# usbSimInput.net
KiCad netlist of a schematic drawn in EAGLE
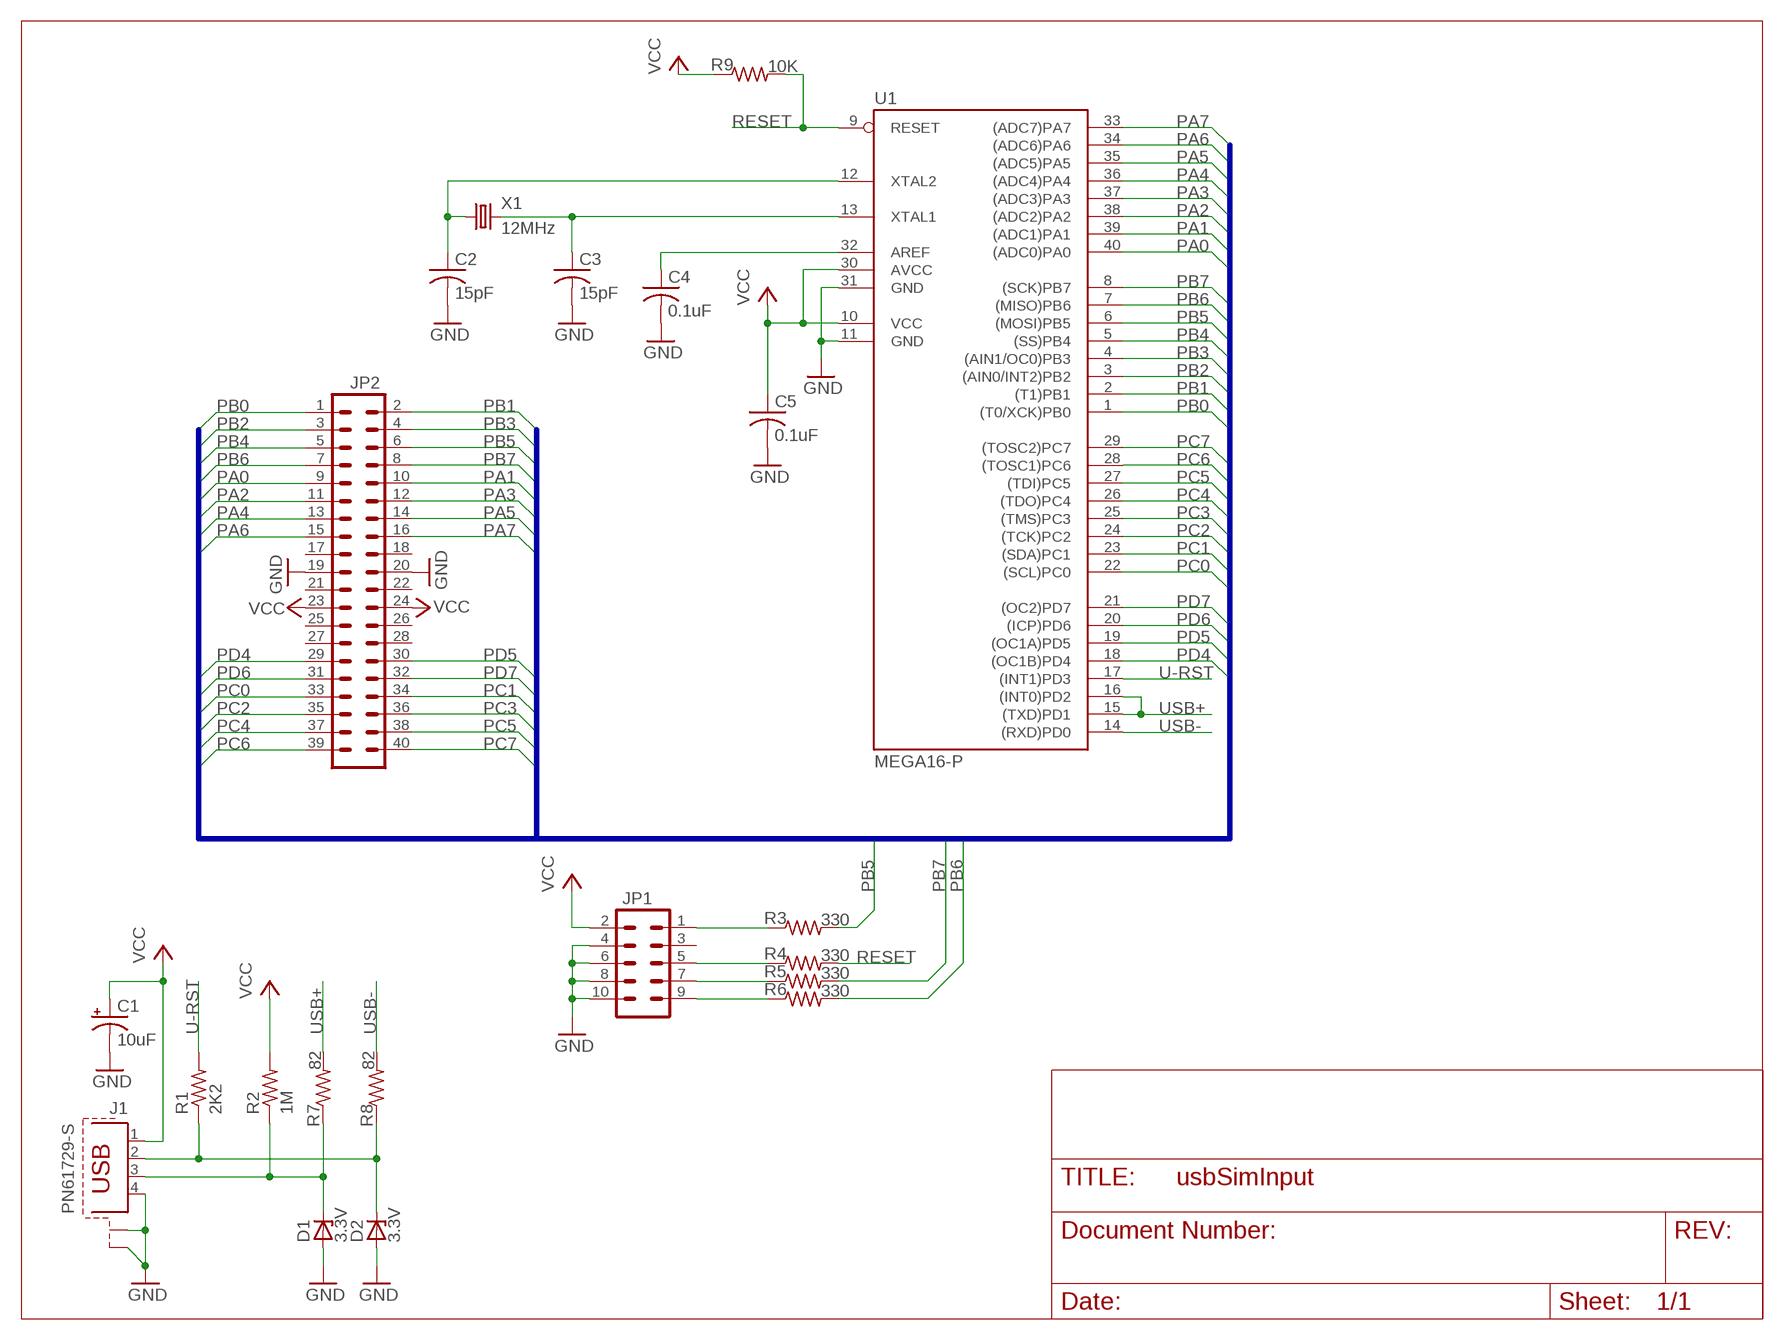
[diagram p0: schematic, sheet 1]

(export (version "E")
  (design (tool "Eeschema 10.0.6"))
  (components
    (comp (ref "C1")
      (value "10uF")
      (footprint "eagle-import:E2,5-5")
      (libsource (lib "eagle-import") (part "CPOL-USE2.5-5"))
    )
    (comp (ref "C2")
      (value "15pF")
      (footprint "eagle-import:C025-024X044")
      (libsource (lib "eagle-import") (part "C-US025-024X044"))
    )
    (comp (ref "C3")
      (value "15pF")
      (footprint "eagle-import:C025-024X044")
      (libsource (lib "eagle-import") (part "C-US025-024X044"))
    )
    (comp (ref "C4")
      (value "0.1uF")
      (footprint "eagle-import:C050-025X075")
      (libsource (lib "eagle-import") (part "C-US050-025X075"))
    )
    (comp (ref "C5")
      (value "0.1uF")
      (footprint "eagle-import:C050-025X075")
      (libsource (lib "eagle-import") (part "C-US050-025X075"))
    )
    (comp (ref "D1")
      (value "3.3V")
      (footprint "eagle-import:ZDIO-5")
      (libsource (lib "eagle-import") (part "ZENER-DIODEZD-5"))
    )
    (comp (ref "D2")
      (value "3.3V")
      (footprint "eagle-import:ZDIO-5")
      (libsource (lib "eagle-import") (part "ZENER-DIODEZD-5"))
    )
    (comp (ref "J1")
      (value "PN61729-S")
      (footprint "eagle-import:PN61729-S")
      (libsource (lib "eagle-import") (part "PN61729-S"))
    )
    (comp (ref "JP1")
      (value "ML10")
      (footprint "eagle-import:ML10")
      (libsource (lib "eagle-import") (part "ML10"))
    )
    (comp (ref "JP2")
      (value "MA20-2")
      (footprint "eagle-import:MA20-2")
      (libsource (lib "eagle-import") (part "MA20-2"))
    )
    (comp (ref "R1")
      (value "2K2")
      (footprint "eagle-import:0207_7")
      (libsource (lib "eagle-import") (part "R-US_0207/7"))
    )
    (comp (ref "R2")
      (value "1M")
      (footprint "eagle-import:0207_7")
      (libsource (lib "eagle-import") (part "R-US_0207/7"))
    )
    (comp (ref "R3")
      (value "330")
      (footprint "eagle-import:0207_7")
      (libsource (lib "eagle-import") (part "R-US_0207/7"))
    )
    (comp (ref "R4")
      (value "330")
      (footprint "eagle-import:0207_7")
      (libsource (lib "eagle-import") (part "R-US_0207/7"))
    )
    (comp (ref "R5")
      (value "330")
      (footprint "eagle-import:0207_7")
      (libsource (lib "eagle-import") (part "R-US_0207/7"))
    )
    (comp (ref "R6")
      (value "330")
      (footprint "eagle-import:0207_7")
      (libsource (lib "eagle-import") (part "R-US_0207/7"))
    )
    (comp (ref "R7")
      (value "82")
      (footprint "eagle-import:0207_7")
      (libsource (lib "eagle-import") (part "R-US_0207/7"))
    )
    (comp (ref "R8")
      (value "82")
      (footprint "eagle-import:0207_7")
      (libsource (lib "eagle-import") (part "R-US_0207/7"))
    )
    (comp (ref "R9")
      (value "10K")
      (footprint "eagle-import:0207_7")
      (libsource (lib "eagle-import") (part "R-US_0207/7"))
    )
    (comp (ref "U1")
      (value "MEGA16-P")
      (footprint "eagle-import:DIL40")
      (fields (field (name "MPN") "ATMEGA16-16PU"))
      (libsource (lib "eagle-import") (part "MEGA16-P"))
    )
    (comp (ref "X1")
      (value "12MHz")
      (footprint "eagle-import:HC49U-V")
      (libsource (lib "eagle-import") (part "CRYSTALHC49U-V"))
    )
  )
  (nets
    (net (code "1") (name "/PA0") (class "Default")
      (node (ref "JP2") (pin "9") (pinfunction "9_9") (pintype "passive"))
      (node (ref "U1") (pin "40") (pinfunction "(ADC0)PA0_40") (pintype "bidirectional"))
    )
    (net (code "2") (name "/PA1") (class "Default")
      (node (ref "JP2") (pin "10") (pinfunction "10_10") (pintype "passive"))
      (node (ref "U1") (pin "39") (pinfunction "(ADC1)PA1_39") (pintype "bidirectional"))
    )
    (net (code "3") (name "/PA2") (class "Default")
      (node (ref "JP2") (pin "11") (pinfunction "11_11") (pintype "passive"))
      (node (ref "U1") (pin "38") (pinfunction "(ADC2)PA2_38") (pintype "bidirectional"))
    )
    (net (code "4") (name "/PA3") (class "Default")
      (node (ref "JP2") (pin "12") (pinfunction "12_12") (pintype "passive"))
      (node (ref "U1") (pin "37") (pinfunction "(ADC3)PA3_37") (pintype "bidirectional"))
    )
    (net (code "5") (name "/PA4") (class "Default")
      (node (ref "JP2") (pin "13") (pinfunction "13_13") (pintype "passive"))
      (node (ref "U1") (pin "36") (pinfunction "(ADC4)PA4_36") (pintype "bidirectional"))
    )
    (net (code "6") (name "/PA5") (class "Default")
      (node (ref "JP2") (pin "14") (pinfunction "14_14") (pintype "passive"))
      (node (ref "U1") (pin "35") (pinfunction "(ADC5)PA5_35") (pintype "bidirectional"))
    )
    (net (code "7") (name "/PA6") (class "Default")
      (node (ref "JP2") (pin "15") (pinfunction "15_15") (pintype "passive"))
      (node (ref "U1") (pin "34") (pinfunction "(ADC6)PA6_34") (pintype "bidirectional"))
    )
    (net (code "8") (name "/PA7") (class "Default")
      (node (ref "JP2") (pin "16") (pinfunction "16_16") (pintype "passive"))
      (node (ref "U1") (pin "33") (pinfunction "(ADC7)PA7_33") (pintype "bidirectional"))
    )
    (net (code "9") (name "/PB0") (class "Default")
      (node (ref "JP2") (pin "1") (pinfunction "1_1") (pintype "passive"))
      (node (ref "U1") (pin "1") (pinfunction "(T0/XCK)PB0_1") (pintype "bidirectional"))
    )
    (net (code "10") (name "/PB1") (class "Default")
      (node (ref "JP2") (pin "2") (pinfunction "2_2") (pintype "passive"))
      (node (ref "U1") (pin "2") (pinfunction "(T1)PB1_2") (pintype "bidirectional"))
    )
    (net (code "11") (name "/PB2") (class "Default")
      (node (ref "JP2") (pin "3") (pinfunction "3_3") (pintype "passive"))
      (node (ref "U1") (pin "3") (pinfunction "(AIN0/INT2)PB2_3") (pintype "bidirectional"))
    )
    (net (code "12") (name "/PB3") (class "Default")
      (node (ref "JP2") (pin "4") (pinfunction "4_4") (pintype "passive"))
      (node (ref "U1") (pin "4") (pinfunction "(AIN1/OC0)PB3_4") (pintype "bidirectional"))
    )
    (net (code "13") (name "/PB4") (class "Default")
      (node (ref "JP2") (pin "5") (pinfunction "5_5") (pintype "passive"))
      (node (ref "U1") (pin "5") (pinfunction "(SS)PB4_5") (pintype "bidirectional"))
    )
    (net (code "14") (name "/PB5") (class "Default")
      (node (ref "JP2") (pin "6") (pinfunction "6_6") (pintype "passive"))
      (node (ref "R3") (pin "2") (pinfunction "2_2") (pintype "passive"))
      (node (ref "U1") (pin "6") (pinfunction "(MOSI)PB5_6") (pintype "bidirectional"))
    )
    (net (code "15") (name "/PB6") (class "Default")
      (node (ref "JP2") (pin "7") (pinfunction "7_7") (pintype "passive"))
      (node (ref "R6") (pin "2") (pinfunction "2_2") (pintype "passive"))
      (node (ref "U1") (pin "7") (pinfunction "(MISO)PB6_7") (pintype "bidirectional"))
    )
    (net (code "16") (name "/PB7") (class "Default")
      (node (ref "JP2") (pin "8") (pinfunction "8_8") (pintype "passive"))
      (node (ref "R5") (pin "2") (pinfunction "2_2") (pintype "passive"))
      (node (ref "U1") (pin "8") (pinfunction "(SCK)PB7_8") (pintype "bidirectional"))
    )
    (net (code "17") (name "/PC0") (class "Default")
      (node (ref "JP2") (pin "33") (pinfunction "33_33") (pintype "passive"))
      (node (ref "U1") (pin "22") (pinfunction "(SCL)PC0_22") (pintype "bidirectional"))
    )
    (net (code "18") (name "/PC1") (class "Default")
      (node (ref "JP2") (pin "34") (pinfunction "34_34") (pintype "passive"))
      (node (ref "U1") (pin "23") (pinfunction "(SDA)PC1_23") (pintype "bidirectional"))
    )
    (net (code "19") (name "/PC2") (class "Default")
      (node (ref "JP2") (pin "35") (pinfunction "35_35") (pintype "passive"))
      (node (ref "U1") (pin "24") (pinfunction "(TCK)PC2_24") (pintype "bidirectional"))
    )
    (net (code "20") (name "/PC3") (class "Default")
      (node (ref "JP2") (pin "36") (pinfunction "36_36") (pintype "passive"))
      (node (ref "U1") (pin "25") (pinfunction "(TMS)PC3_25") (pintype "bidirectional"))
    )
    (net (code "21") (name "/PC4") (class "Default")
      (node (ref "JP2") (pin "37") (pinfunction "37_37") (pintype "passive"))
      (node (ref "U1") (pin "26") (pinfunction "(TDO)PC4_26") (pintype "bidirectional"))
    )
    (net (code "22") (name "/PC5") (class "Default")
      (node (ref "JP2") (pin "38") (pinfunction "38_38") (pintype "passive"))
      (node (ref "U1") (pin "27") (pinfunction "(TDI)PC5_27") (pintype "bidirectional"))
    )
    (net (code "23") (name "/PC6") (class "Default")
      (node (ref "JP2") (pin "39") (pinfunction "39_39") (pintype "passive"))
      (node (ref "U1") (pin "28") (pinfunction "(TOSC1)PC6_28") (pintype "bidirectional"))
    )
    (net (code "24") (name "/PC7") (class "Default")
      (node (ref "JP2") (pin "40") (pinfunction "40_40") (pintype "passive"))
      (node (ref "U1") (pin "29") (pinfunction "(TOSC2)PC7_29") (pintype "bidirectional"))
    )
    (net (code "25") (name "/PD4") (class "Default")
      (node (ref "JP2") (pin "29") (pinfunction "29_29") (pintype "passive"))
      (node (ref "U1") (pin "18") (pinfunction "(OC1B)PD4_18") (pintype "bidirectional"))
    )
    (net (code "26") (name "/PD5") (class "Default")
      (node (ref "JP2") (pin "30") (pinfunction "30_30") (pintype "passive"))
      (node (ref "U1") (pin "19") (pinfunction "(OC1A)PD5_19") (pintype "bidirectional"))
    )
    (net (code "27") (name "/PD6") (class "Default")
      (node (ref "JP2") (pin "31") (pinfunction "31_31") (pintype "passive"))
      (node (ref "U1") (pin "20") (pinfunction "(ICP)PD6_20") (pintype "bidirectional"))
    )
    (net (code "28") (name "/PD7") (class "Default")
      (node (ref "JP2") (pin "32") (pinfunction "32_32") (pintype "passive"))
      (node (ref "U1") (pin "21") (pinfunction "(OC2)PD7_21") (pintype "bidirectional"))
    )
    (net (code "29") (name "/RESET") (class "Default")
      (node (ref "R4") (pin "2") (pinfunction "2_2") (pintype "passive"))
      (node (ref "R9") (pin "2") (pinfunction "2_2") (pintype "passive"))
      (node (ref "U1") (pin "9") (pinfunction "RESET_9") (pintype "input"))
    )
    (net (code "30") (name "/U-RST") (class "Default")
      (node (ref "R1") (pin "2") (pinfunction "2_2") (pintype "passive"))
      (node (ref "U1") (pin "17") (pinfunction "(INT1)PD3_17") (pintype "bidirectional"))
    )
    (net (code "31") (name "/USB+") (class "Default")
      (node (ref "R7") (pin "2") (pinfunction "2_2") (pintype "passive"))
      (node (ref "U1") (pin "15") (pinfunction "(TXD)PD1_15") (pintype "bidirectional"))
      (node (ref "U1") (pin "16") (pinfunction "(INT0)PD2_16") (pintype "bidirectional"))
    )
    (net (code "32") (name "/USB-") (class "Default")
      (node (ref "R8") (pin "2") (pinfunction "2_2") (pintype "passive"))
      (node (ref "U1") (pin "14") (pinfunction "(RXD)PD0_14") (pintype "bidirectional"))
    )
    (net (code "33") (name "GND") (class "Default")
      (node (ref "C1") (pin "-") (pinfunction "-_-") (pintype "passive"))
      (node (ref "C2") (pin "2") (pinfunction "2_2") (pintype "passive"))
      (node (ref "C3") (pin "2") (pinfunction "2_2") (pintype "passive"))
      (node (ref "C4") (pin "2") (pinfunction "2_2") (pintype "passive"))
      (node (ref "C5") (pin "2") (pinfunction "2_2") (pintype "passive"))
      (node (ref "D1") (pin "A") (pinfunction "A_A") (pintype "passive"))
      (node (ref "D2") (pin "A") (pinfunction "A_A") (pintype "passive"))
      (node (ref "J1") (pin "4") (pinfunction "4_4") (pintype "passive"))
      (node (ref "J1") (pin "S1") (pinfunction "S1_S1") (pintype "passive"))
      (node (ref "J1") (pin "S2") (pinfunction "S2_S2") (pintype "passive"))
      (node (ref "JP1") (pin "10") (pinfunction "10_10") (pintype "passive"))
      (node (ref "JP1") (pin "4") (pinfunction "4_4") (pintype "passive"))
      (node (ref "JP1") (pin "6") (pinfunction "6_6") (pintype "passive"))
      (node (ref "JP1") (pin "8") (pinfunction "8_8") (pintype "passive"))
      (node (ref "JP2") (pin "19") (pinfunction "19_19") (pintype "passive"))
      (node (ref "JP2") (pin "20") (pinfunction "20_20") (pintype "passive"))
      (node (ref "U1") (pin "11") (pinfunction "GND_11") (pintype "power_in"))
      (node (ref "U1") (pin "31") (pinfunction "GND_31") (pintype "power_in"))
    )
    (net (code "34") (name "Net-(D1-PadC)") (class "Default")
      (node (ref "D1") (pin "C") (pinfunction "C_C") (pintype "passive"))
      (node (ref "J1") (pin "3") (pinfunction "3_3") (pintype "passive"))
      (node (ref "R2") (pin "1") (pinfunction "1_1") (pintype "passive"))
      (node (ref "R7") (pin "1") (pinfunction "1_1") (pintype "passive"))
    )
    (net (code "35") (name "Net-(D2-PadC)") (class "Default")
      (node (ref "D2") (pin "C") (pinfunction "C_C") (pintype "passive"))
      (node (ref "J1") (pin "2") (pinfunction "2_2") (pintype "passive"))
      (node (ref "R1") (pin "1") (pinfunction "1_1") (pintype "passive"))
      (node (ref "R8") (pin "1") (pinfunction "1_1") (pintype "passive"))
    )
    (net (code "36") (name "Net-(JP1-Pad1)") (class "Default")
      (node (ref "JP1") (pin "1") (pinfunction "1_1") (pintype "passive"))
      (node (ref "R3") (pin "1") (pinfunction "1_1") (pintype "passive"))
    )
    (net (code "37") (name "Net-(JP1-Pad5)") (class "Default")
      (node (ref "JP1") (pin "5") (pinfunction "5_5") (pintype "passive"))
      (node (ref "R4") (pin "1") (pinfunction "1_1") (pintype "passive"))
    )
    (net (code "38") (name "Net-(JP1-Pad7)") (class "Default")
      (node (ref "JP1") (pin "7") (pinfunction "7_7") (pintype "passive"))
      (node (ref "R5") (pin "1") (pinfunction "1_1") (pintype "passive"))
    )
    (net (code "39") (name "Net-(JP1-Pad9)") (class "Default")
      (node (ref "JP1") (pin "9") (pinfunction "9_9") (pintype "passive"))
      (node (ref "R6") (pin "1") (pinfunction "1_1") (pintype "passive"))
    )
    (net (code "40") (name "Net-(U1-AREF)") (class "Default")
      (node (ref "C4") (pin "1") (pinfunction "1_1") (pintype "passive"))
      (node (ref "U1") (pin "32") (pinfunction "AREF_32") (pintype "passive"))
    )
    (net (code "41") (name "Net-(U1-XTAL1)") (class "Default")
      (node (ref "C3") (pin "1") (pinfunction "1_1") (pintype "passive"))
      (node (ref "U1") (pin "13") (pinfunction "XTAL1_13") (pintype "bidirectional"))
      (node (ref "X1") (pin "2") (pinfunction "2_2") (pintype "passive"))
    )
    (net (code "42") (name "Net-(U1-XTAL2)") (class "Default")
      (node (ref "C2") (pin "1") (pinfunction "1_1") (pintype "passive"))
      (node (ref "U1") (pin "12") (pinfunction "XTAL2_12") (pintype "bidirectional"))
      (node (ref "X1") (pin "1") (pinfunction "1_1") (pintype "passive"))
    )
    (net (code "43") (name "VCC") (class "Default")
      (node (ref "C1") (pin "+") (pinfunction "+_+") (pintype "passive"))
      (node (ref "C5") (pin "1") (pinfunction "1_1") (pintype "passive"))
      (node (ref "J1") (pin "1") (pinfunction "1_1") (pintype "passive"))
      (node (ref "JP1") (pin "2") (pinfunction "2_2") (pintype "passive"))
      (node (ref "JP2") (pin "23") (pinfunction "23_23") (pintype "passive"))
      (node (ref "JP2") (pin "24") (pinfunction "24_24") (pintype "passive"))
      (node (ref "R2") (pin "2") (pinfunction "2_2") (pintype "passive"))
      (node (ref "R9") (pin "1") (pinfunction "1_1") (pintype "passive"))
      (node (ref "U1") (pin "10") (pinfunction "VCC_10") (pintype "power_in"))
      (node (ref "U1") (pin "30") (pinfunction "AVCC_30") (pintype "power_in"))
    )
    (net (code "44") (name "unconnected-(JP1-Pad3)") (class "Default")
      (node (ref "JP1") (pin "3") (pinfunction "3_3") (pintype "passive"))
    )
    (net (code "45") (name "unconnected-(JP2-Pad17)") (class "Default")
      (node (ref "JP2") (pin "17") (pinfunction "17_17") (pintype "passive"))
    )
    (net (code "46") (name "unconnected-(JP2-Pad18)") (class "Default")
      (node (ref "JP2") (pin "18") (pinfunction "18_18") (pintype "passive"))
    )
    (net (code "47") (name "unconnected-(JP2-Pad21)") (class "Default")
      (node (ref "JP2") (pin "21") (pinfunction "21_21") (pintype "passive"))
    )
    (net (code "48") (name "unconnected-(JP2-Pad22)") (class "Default")
      (node (ref "JP2") (pin "22") (pinfunction "22_22") (pintype "passive"))
    )
    (net (code "49") (name "unconnected-(JP2-Pad25)") (class "Default")
      (node (ref "JP2") (pin "25") (pinfunction "25_25") (pintype "passive"))
    )
    (net (code "50") (name "unconnected-(JP2-Pad26)") (class "Default")
      (node (ref "JP2") (pin "26") (pinfunction "26_26") (pintype "passive"))
    )
    (net (code "51") (name "unconnected-(JP2-Pad27)") (class "Default")
      (node (ref "JP2") (pin "27") (pinfunction "27_27") (pintype "passive"))
    )
    (net (code "52") (name "unconnected-(JP2-Pad28)") (class "Default")
      (node (ref "JP2") (pin "28") (pinfunction "28_28") (pintype "passive"))
    )
  )
)
